# vaja1.net
KiCad netlist of a schematic drawn in Altium Designer
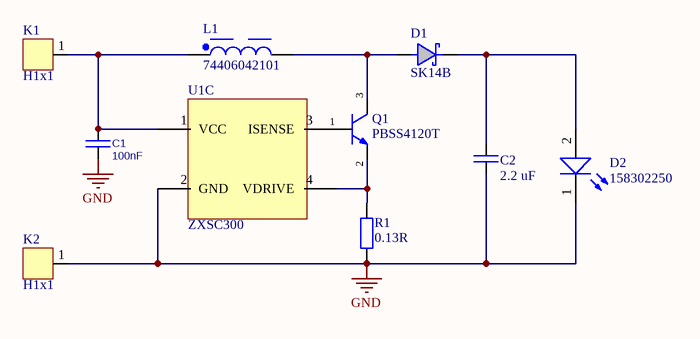
[diagram p0: vaja1.SchDoc]

(export (version "E")
  (design (tool "Eeschema 10.0.6"))
  (components
    (comp (ref "C1")
      (value "100nF")
      (footprint "C0805")
      (description "Capacitor")
      (libsource (lib "University of Ljubljana, Faculty of Electrical Engineering") (part "C"))
    )
    (comp (ref "C2")
      (value "2.2 uF")
      (footprint "C0805(2012)_M")
      (description "Capacitor")
      (fields (field (name "SOURCE") "MISKO.SCHLIB"))
      (libsource (lib "University of Ljubljana, Faculty of Electrical Engineering") (part "Symbol"))
    )
    (comp (ref "D1")
      (value "SK14B")
      (footprint "DO-214AA_SMB_N")
      (libsource (lib "generic library") (part "Diode Schottky"))
    )
    (comp (ref "D2")
      (value "158302250")
      (footprint "WL-SWTP_3022_L3W2H0.8")
      (description "WL-SWTP SMT White Top view PLCC, size 3022, Daylight, 3.2V, 120°")
      (fields (field (name "MANUFACTURER") "Wurth Elektronik"))
      (libsource (lib "University of Ljubljana, Faculty of Electrical Engineering") (part "158563260A"))
    )
    (comp (ref "K1")
      (value "H1x1")
      (footprint "H1x1")
      (description "Header 1x1 (male)")
      (libsource (lib "University of Ljubljana, Faculty of Electrical Engineering") (part "H1x1"))
    )
    (comp (ref "K2")
      (value "H1x1")
      (footprint "H1x1")
      (description "Header 1x1 (male)")
      (libsource (lib "University of Ljubljana, Faculty of Electrical Engineering") (part "H1x1"))
    )
    (comp (ref "L1")
      (value "74406042101")
      (footprint "WE-LQFS_4818")
      (description "WE-LQFS SMT Power Inductor, size 4818, 100µH, 0.42A, 1386mO")
      (fields (field (name "MANUFACTURER") "Wurth Elektronik"))
      (libsource (lib "University of Ljubljana, Faculty of Electrical Engineering") (part "74406043471"))
    )
    (comp (ref "Q1")
      (value "PBSS4120T")
      (footprint "SOT23-3_N")
      (libsource (lib "generic library") (part "Transistor BJT NPN"))
    )
    (comp (ref "R1")
      (value "0.13R")
      (footprint "R0805(2012)_M")
      (description "R")
      (fields (field (name "SOURCE") "MISKO.SCHLIB"))
      (libsource (lib "") (part "Symbol_1"))
    )
    (comp (ref "U1")
      (value "ZXSC300")
      (libsource (lib "University of Ljubljana, Faculty of Electrical Engineering") (part "ZXSC300"))
    )
  )
  (nets
    (net (code "1") (name "GND") (class "Default")
      (node (ref "C1") (pin "2") (pinfunction "2_2") (pintype "passive"))
      (node (ref "C2") (pin "2") (pinfunction "2_2") (pintype "passive"))
      (node (ref "D2") (pin "1") (pinfunction "K_1") (pintype "passive"))
      (node (ref "K2") (pin "1") (pinfunction "1_1") (pintype "passive"))
      (node (ref "R1") (pin "2") (pintype "passive"))
    )
    (net (code "2") (name "Net-(C1-Pad1)") (class "Default")
      (node (ref "C1") (pin "1") (pinfunction "1_1") (pintype "passive"))
      (node (ref "K1") (pin "1") (pinfunction "1_1") (pintype "passive"))
      (node (ref "L1") (pin "1") (pinfunction "1_1") (pintype "passive"))
    )
    (net (code "3") (name "Net-(D2-A)") (class "Default")
      (node (ref "C2") (pin "1") (pinfunction "1_1") (pintype "passive"))
      (node (ref "D1") (pin "C") (pinfunction "C_C") (pintype "passive"))
      (node (ref "D2") (pin "2") (pinfunction "A_2") (pintype "passive"))
    )
    (net (code "4") (name "Net-(Q1-C)") (class "Default")
      (node (ref "D1") (pin "A") (pinfunction "A_A") (pintype "passive"))
      (node (ref "L1") (pin "2") (pinfunction "2_2") (pintype "passive"))
      (node (ref "Q1") (pin "3") (pinfunction "C_3") (pintype "passive"))
    )
    (net (code "5") (name "Net-(Q1-E)") (class "Default")
      (node (ref "Q1") (pin "2") (pinfunction "E_2") (pintype "passive"))
      (node (ref "R1") (pin "1") (pintype "passive"))
      (node (ref "U1") (pin "4") (pinfunction "VDRIVE_4") (pintype "passive"))
    )
    (net (code "6") (name "unconnected-(Q1-B-Pad1)") (class "Default")
      (node (ref "Q1") (pin "1") (pinfunction "B_1") (pintype "passive"))
    )
    (net (code "7") (name "unconnected-(U1C-GND-Pad2)") (class "Default")
      (node (ref "U1") (pin "2") (pinfunction "GND_2") (pintype "passive"))
    )
    (net (code "8") (name "unconnected-(U1C-ISENSE-Pad3)") (class "Default")
      (node (ref "U1") (pin "3") (pinfunction "ISENSE_3") (pintype "passive"))
    )
    (net (code "9") (name "unconnected-(U1C-VCC-Pad1)") (class "Default")
      (node (ref "U1") (pin "1") (pinfunction "VCC_1") (pintype "passive"))
    )
  )
)
